# Schematic.net
KiCad netlist of a schematic drawn in Altium Designer
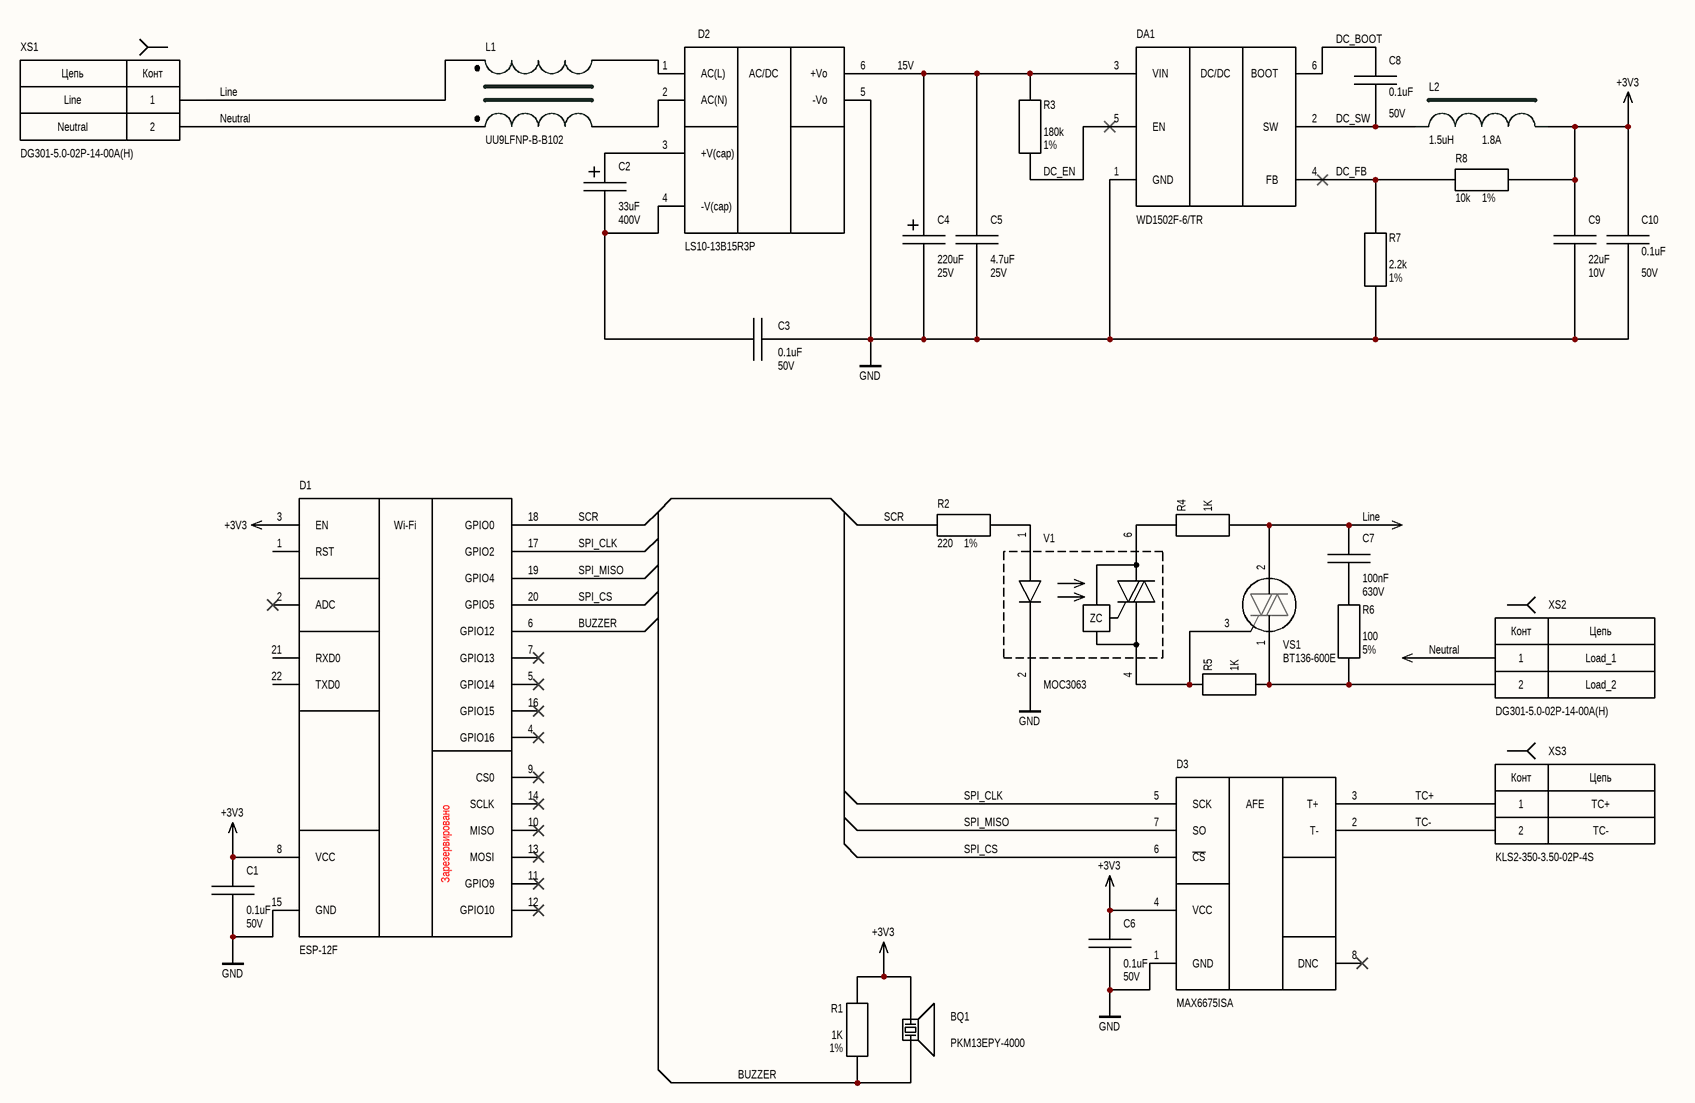
[diagram p0: Schematic.SchDoc]

(export (version "E")
  (design (tool "Eeschema 10.0.6"))
  (components
    (comp (ref "BQ1")
      (value "PKM13EPY-4000")
      (footprint "R_D12p6_H6p9_S5_d0p5")
      (fields (field (name "MANUFACTURER") "Murata"))
      (libsource (lib "CircuitCraft") (part "Buzzer"))
    )
    (comp (ref "C1")
      (value "0.1uF")
      (footprint "CAPC1608X09N")
      (fields
        (field (name "PART NUMBER") "0603-0.1uF-50V-10%-X7R")
        (field (name "VOLTAGE") "50V")
        (field (name "TOLERANCE") "10%")
        (field (name "PARAMETER") "50V")
      )
      (libsource (lib "CircuitCraft") (part "Capacitor"))
    )
    (comp (ref "C2")
      (value "33uF")
      (fields
        (field (name "PARAMETER") "400V")
        (field (name "PART NUMBER") "SHG33UF400V01EC1480")
        (field (name "MANUFACTURER") "KNSCHA")
        (field (name "VOLTAGE") "400V")
      )
      (libsource (lib "CircuitCraft") (part "Capacitor_pol"))
    )
    (comp (ref "C3")
      (value "0.1uF")
      (footprint "CAPC1608X09N")
      (fields
        (field (name "PART NUMBER") "0603-0.1uF-50V-10%-X7R")
        (field (name "VOLTAGE") "50V")
        (field (name "TOLERANCE") "10%")
        (field (name "PARAMETER") "50V")
      )
      (libsource (lib "CircuitCraft") (part "Capacitor"))
    )
    (comp (ref "C4")
      (value "220uF")
      (fields
        (field (name "PARAMETER") "25V")
        (field (name "PART NUMBER") "03EC0360")
        (field (name "MANUFACTURER") "KNSCHA")
        (field (name "VOLTAGE") "25V")
      )
      (libsource (lib "CircuitCraft") (part "Capacitor_pol"))
    )
    (comp (ref "C5")
      (value "4.7uF")
      (footprint "CAPC3216X19N")
      (fields
        (field (name "PARAMETER") "25V")
        (field (name "PART NUMBER") "1206-4.7uF-25V-10%-X7R")
        (field (name "VOLTAGE") "25V")
        (field (name "TOLERANCE") "10%")
      )
      (libsource (lib "CircuitCraft") (part "Capacitor"))
    )
    (comp (ref "C6")
      (value "0.1uF")
      (footprint "CAPC1608X09N")
      (fields
        (field (name "PART NUMBER") "0603-0.1uF-50V-10%-X7R")
        (field (name "VOLTAGE") "50V")
        (field (name "TOLERANCE") "10%")
        (field (name "PARAMETER") "50V")
      )
      (libsource (lib "CircuitCraft") (part "Capacitor"))
    )
    (comp (ref "C7")
      (value "100nF")
      (footprint "CAPRR1600W70L1750T600H1200")
      (fields
        (field (name "PARAMETER") "630V")
        (field (name "PART NUMBER") "MEF104J2J6AS6040A1")
        (field (name "MANUFACTURER") "JOEY")
        (field (name "VOLTAGE") "630V")
      )
      (libsource (lib "CircuitCraft") (part "Capacitor"))
    )
    (comp (ref "C8")
      (value "0.1uF")
      (footprint "CAPC1608X09N")
      (fields
        (field (name "PART NUMBER") "0603-0.1uF-50V-10%-X7R")
        (field (name "VOLTAGE") "50V")
        (field (name "TOLERANCE") "10%")
        (field (name "PARAMETER") "50V")
      )
      (libsource (lib "CircuitCraft") (part "Capacitor"))
    )
    (comp (ref "C9")
      (value "22uF")
      (footprint "CAPC3216X19N")
      (fields
        (field (name "PARAMETER") "10V")
        (field (name "PART NUMBER") "1206-22uF-10V-10%-X7R")
        (field (name "VOLTAGE") "10V")
        (field (name "TOLERANCE") "10%")
      )
      (libsource (lib "CircuitCraft") (part "Capacitor"))
    )
    (comp (ref "C10")
      (value "0.1uF")
      (footprint "CAPC1608X09N")
      (fields
        (field (name "PART NUMBER") "0603-0.1uF-50V-10%-X7R")
        (field (name "VOLTAGE") "50V")
        (field (name "TOLERANCE") "10%")
        (field (name "PARAMETER") "50V")
      )
      (libsource (lib "CircuitCraft") (part "Capacitor"))
    )
    (comp (ref "D1")
      (value "ESP-12F")
      (footprint "ESP-12F")
      (fields (field (name "MANUFACTURER") "Ai-Thinker"))
      (libsource (lib "CircuitCraft") (part "ESP-12F"))
    )
    (comp (ref "D2")
      (value "LS10-13B15R3P")
      (footprint "LS10-13BxxR3P_LUT")
      (fields (field (name "MANUFACTURER") "MORNSUN Guangzhou S& T"))
      (libsource (lib "CircuitCraft") (part "LS10-13BxxR3P"))
    )
    (comp (ref "D3")
      (value "MAX6675ISA")
      (footprint "SOIC8P127_490X600X175L83X42N")
      (fields (field (name "MANUFACTURER") "Analog Devices Inc./Maxim Integrated"))
      (libsource (lib "CircuitCraft") (part "MAX6675ISA"))
    )
    (comp (ref "DA1")
      (value "WD1502F-6/TR")
      (footprint "SOT23-6P95_280X90L45X42N")
      (fields (field (name "MANUFACTURER") "WILLSEMI(Will Semicon)"))
      (libsource (lib "CircuitCraft") (part "WD1502F-6_TR"))
    )
    (comp (ref "L1")
      (value "UU9LFNP-B-B102")
      (footprint "UU9LF")
      (fields (field (name "MANUFACTURER") "Sumida"))
      (libsource (lib "CircuitCraft") (part "Common Mode Choke"))
    )
    (comp (ref "L2")
      (value "1.5uH")
      (footprint "INDP400L400WX180_N")
      (fields
        (field (name "PARAMETER") "1.8A")
        (field (name "PART NUMBER") "SWPA4018S1R5NT")
        (field (name "MANUFACTURER") "Sunlord")
        (field (name "TOLERANCE") "30%")
      )
      (libsource (lib "CircuitCraft") (part "Inductor"))
    )
    (comp (ref "R1")
      (value "1K")
      (footprint "RESC1608X55N")
      (description "Resistor")
      (fields
        (field (name "PART NUMBER") "0603-1K-1%-1/10 W-100ppm")
        (field (name "TOLERANCE") "1%")
        (field (name "PARAMETER") "1%")
      )
      (libsource (lib "CircuitCraft") (part "Resistor"))
    )
    (comp (ref "R2")
      (value "220")
      (footprint "RESC1608X55N")
      (description "Resistor")
      (fields
        (field (name "PART NUMBER") "0603-220-1%-1/10 W-100ppm")
        (field (name "TOLERANCE") "1%")
        (field (name "PARAMETER") "1%")
      )
      (libsource (lib "CircuitCraft") (part "Resistor"))
    )
    (comp (ref "R3")
      (value "180k")
      (footprint "RESC1608X55N")
      (description "Resistor")
      (fields
        (field (name "PARAMETER") "1%")
        (field (name "PART NUMBER") "0603-180K-1%-1/10W-100ppm")
        (field (name "TOLERANCE") "1%")
      )
      (libsource (lib "CircuitCraft") (part "Resistor"))
    )
    (comp (ref "R4")
      (value "1K")
      (footprint "RESC1608X55N")
      (description "Resistor")
      (fields (field (name "PART NUMBER") "0603-1K-1%-1/10 W-100ppm") (field (name "TOLERANCE") "1%"))
      (libsource (lib "CircuitCraft") (part "Resistor"))
    )
    (comp (ref "R5")
      (value "1K")
      (footprint "RESC1608X55N")
      (description "Resistor")
      (fields (field (name "PART NUMBER") "0603-1K-1%-1/10 W-100ppm") (field (name "TOLERANCE") "1%"))
      (libsource (lib "CircuitCraft") (part "Resistor"))
    )
    (comp (ref "R6")
      (value "100")
      (footprint "MF-05W_RESAD1400W60L1000D500")
      (description "Resistor")
      (fields
        (field (name "PARAMETER") "5%")
        (field (name "PART NUMBER") "MF0W2JJ0101A10")
        (field (name "MANUFACTURER") "UNI-ROYAL(Uniroyal Elec)")
      )
      (libsource (lib "CircuitCraft") (part "Resistor"))
    )
    (comp (ref "R7")
      (value "2.2k")
      (footprint "RESC1608X55N")
      (description "Resistor")
      (fields
        (field (name "PARAMETER") "1%")
        (field (name "PART NUMBER") "0603-2.2K-1%-1/10W-100ppm")
        (field (name "TOLERANCE") "1%")
      )
      (libsource (lib "CircuitCraft") (part "Resistor"))
    )
    (comp (ref "R8")
      (value "10k")
      (footprint "RESC1608X55N")
      (description "Resistor")
      (fields
        (field (name "PARAMETER") "1%")
        (field (name "PART NUMBER") "0603-10k-1%-1/10 W-100ppm")
        (field (name "TOLERANCE") "1%")
      )
      (libsource (lib "CircuitCraft") (part "Resistor"))
    )
    (comp (ref "V1")
      (value "MOC3063")
      (footprint "DIP-6_DIP762W50P254L735H400Q6")
      (description "Оптрон тиристорный")
      (fields (field (name "MANUFACTURER") "Lite-On"))
      (libsource (lib "CircuitCraft") (part "MOC3063"))
    )
    (comp (ref "VS1")
      (value "BT136-600Е")
      (footprint "TO-220C_TO254_440P1040X460X2000-3")
      (fields (field (name "MANUFACTURER") "WEIDA"))
      (libsource (lib "CircuitCraft") (part "Triac_1T12T23G"))
    )
    (comp (ref "XS1")
      (value "DG301-5.0-02P-14-00A(H)")
      (footprint "DG301-5.0-02P")
      (fields (field (name "MANUFACTURER") "DEGSON"))
      (libsource (lib "CircuitCraft") (part "CONN_2PIN_F"))
    )
    (comp (ref "XS2")
      (value "DG301-5.0-02P-14-00A(H)")
      (footprint "DG301-5.0-02P")
      (fields (field (name "MANUFACTURER") "DEGSON"))
      (libsource (lib "CircuitCraft") (part "CONN_2PIN_F"))
    )
    (comp (ref "XS3")
      (value "KLS2-350-3.50-02P-4S")
      (footprint "KLS2-350-3.50-02P-4S")
      (fields (field (name "MANUFACTURER") "KLS"))
      (libsource (lib "CircuitCraft") (part "CONN_2PIN_F"))
    )
  )
  (nets
    (net (code "1") (name "+3V3") (class "Default")
      (node (ref "BQ1") (pin "1") (pinfunction "1_1") (pintype "passive"))
      (node (ref "C1") (pin "1") (pinfunction "1_1") (pintype "passive"))
      (node (ref "C10") (pin "1") (pinfunction "1_1") (pintype "passive"))
      (node (ref "C6") (pin "1") (pinfunction "1_1") (pintype "passive"))
      (node (ref "C9") (pin "1") (pinfunction "1_1") (pintype "passive"))
      (node (ref "D1") (pin "3") (pinfunction "EN_3") (pintype "passive"))
      (node (ref "D1") (pin "8") (pinfunction "VCC_8") (pintype "passive"))
      (node (ref "D3") (pin "4") (pinfunction "VCC_4") (pintype "passive"))
      (node (ref "L2") (pin "2") (pinfunction "2_2") (pintype "passive"))
      (node (ref "R1") (pin "2") (pinfunction "2_2") (pintype "passive"))
      (node (ref "R8") (pin "2") (pinfunction "2_2") (pintype "passive"))
    )
    (net (code "2") (name "/15V") (class "Default")
      (node (ref "C4") (pin "2") (pinfunction "2_2") (pintype "passive"))
      (node (ref "C5") (pin "1") (pinfunction "1_1") (pintype "passive"))
      (node (ref "D2") (pin "6") (pinfunction "+Vo_6") (pintype "passive"))
      (node (ref "DA1") (pin "3") (pinfunction "VIN_3") (pintype "passive"))
      (node (ref "R3") (pin "2") (pinfunction "2_2") (pintype "passive"))
    )
    (net (code "3") (name "/BUZZER") (class "Default")
      (node (ref "BQ1") (pin "2") (pinfunction "2_2") (pintype "passive"))
      (node (ref "D1") (pin "6") (pinfunction "GPIO12_6") (pintype "passive"))
      (node (ref "R1") (pin "1") (pinfunction "1_1") (pintype "passive"))
    )
    (net (code "4") (name "/DC_BOOT") (class "Default")
      (node (ref "C8") (pin "1") (pinfunction "1_1") (pintype "passive"))
      (node (ref "DA1") (pin "6") (pinfunction "BOOT_6") (pintype "passive"))
    )
    (net (code "5") (name "/DC_EN") (class "Default")
      (node (ref "DA1") (pin "5") (pinfunction "EN_5") (pintype "passive"))
      (node (ref "R3") (pin "1") (pinfunction "1_1") (pintype "passive"))
    )
    (net (code "6") (name "/DC_FB") (class "Default")
      (node (ref "DA1") (pin "4") (pinfunction "FB_4") (pintype "passive"))
      (node (ref "R7") (pin "2") (pinfunction "2_2") (pintype "passive"))
      (node (ref "R8") (pin "1") (pinfunction "1_1") (pintype "passive"))
    )
    (net (code "7") (name "/DC_SW") (class "Default")
      (node (ref "C8") (pin "2") (pinfunction "2_2") (pintype "passive"))
      (node (ref "DA1") (pin "2") (pinfunction "SW_2") (pintype "passive"))
      (node (ref "L2") (pin "1") (pinfunction "1_1") (pintype "passive"))
    )
    (net (code "8") (name "/Line") (class "Default")
      (node (ref "C7") (pin "1") (pinfunction "1_1") (pintype "passive"))
      (node (ref "L1") (pin "1") (pinfunction "1_1") (pintype "passive"))
      (node (ref "R4") (pin "1") (pinfunction "1_1") (pintype "passive"))
      (node (ref "VS1") (pin "2") (pinfunction "T2_2") (pintype "passive"))
      (node (ref "XS1") (pin "1") (pinfunction "1_1") (pintype "passive"))
    )
    (net (code "9") (name "/Neutral") (class "Default")
      (node (ref "L1") (pin "4") (pinfunction "4_4") (pintype "passive"))
      (node (ref "XS1") (pin "2") (pinfunction "2_2") (pintype "passive"))
      (node (ref "XS2") (pin "1") (pinfunction "1_1") (pintype "passive"))
    )
    (net (code "10") (name "/SCR") (class "Default")
      (node (ref "D1") (pin "18") (pinfunction "GPIO0_18") (pintype "passive"))
      (node (ref "R2") (pin "1") (pinfunction "1_1") (pintype "passive"))
    )
    (net (code "11") (name "/SPI_CLK") (class "Default")
      (node (ref "D1") (pin "17") (pinfunction "GPIO2_17") (pintype "passive"))
      (node (ref "D3") (pin "5") (pinfunction "SCK_5") (pintype "passive"))
    )
    (net (code "12") (name "/SPI_CS") (class "Default")
      (node (ref "D1") (pin "20") (pinfunction "GPIO5_20") (pintype "passive"))
      (node (ref "D3") (pin "6") (pinfunction "~{CS}_6") (pintype "passive"))
    )
    (net (code "13") (name "/SPI_MISO") (class "Default")
      (node (ref "D1") (pin "19") (pinfunction "GPIO4_19") (pintype "passive"))
      (node (ref "D3") (pin "7") (pinfunction "SO_7") (pintype "passive"))
    )
    (net (code "14") (name "/TC+") (class "Default")
      (node (ref "D3") (pin "3") (pinfunction "T+_3") (pintype "passive"))
      (node (ref "XS3") (pin "1") (pinfunction "1_1") (pintype "passive"))
    )
    (net (code "15") (name "/TC-") (class "Default")
      (node (ref "D3") (pin "2") (pinfunction "T-_2") (pintype "passive"))
      (node (ref "XS3") (pin "2") (pinfunction "2_2") (pintype "passive"))
    )
    (net (code "16") (name "GND") (class "Default")
      (node (ref "C1") (pin "2") (pinfunction "2_2") (pintype "passive"))
      (node (ref "C10") (pin "2") (pinfunction "2_2") (pintype "passive"))
      (node (ref "C3") (pin "2") (pinfunction "2_2") (pintype "passive"))
      (node (ref "C4") (pin "1") (pinfunction "1_1") (pintype "passive"))
      (node (ref "C5") (pin "2") (pinfunction "2_2") (pintype "passive"))
      (node (ref "C6") (pin "2") (pinfunction "2_2") (pintype "passive"))
      (node (ref "C9") (pin "2") (pinfunction "2_2") (pintype "passive"))
      (node (ref "D1") (pin "15") (pinfunction "GND_15") (pintype "passive"))
      (node (ref "D2") (pin "5") (pinfunction "-Vo_5") (pintype "passive"))
      (node (ref "D3") (pin "1") (pinfunction "GND_1") (pintype "passive"))
      (node (ref "DA1") (pin "1") (pinfunction "GND_1") (pintype "passive"))
      (node (ref "R7") (pin "1") (pinfunction "1_1") (pintype "passive"))
      (node (ref "V1") (pin "2") (pinfunction "-_2") (pintype "passive"))
    )
    (net (code "17") (name "Net-(C7-Pad2)") (class "Default")
      (node (ref "C7") (pin "2") (pinfunction "2_2") (pintype "passive"))
      (node (ref "R6") (pin "2") (pinfunction "2_2") (pintype "passive"))
    )
    (net (code "18") (name "Net-(D2-+V(cap))") (class "Default")
      (node (ref "C2") (pin "2") (pinfunction "2_2") (pintype "passive"))
      (node (ref "D2") (pin "3") (pinfunction "+V(cap)_3") (pintype "passive"))
    )
    (net (code "19") (name "Net-(D2--V(cap))") (class "Default")
      (node (ref "C2") (pin "1") (pinfunction "1_1") (pintype "passive"))
      (node (ref "C3") (pin "1") (pinfunction "1_1") (pintype "passive"))
      (node (ref "D2") (pin "4") (pinfunction "-V(cap)_4") (pintype "passive"))
    )
    (net (code "20") (name "Net-(D2-AC(L))") (class "Default")
      (node (ref "D2") (pin "1") (pinfunction "AC(L)_1") (pintype "passive"))
      (node (ref "L1") (pin "2") (pinfunction "2_2") (pintype "passive"))
    )
    (net (code "21") (name "Net-(D2-AC(N))") (class "Default")
      (node (ref "D2") (pin "2") (pinfunction "AC(N)_2") (pintype "passive"))
      (node (ref "L1") (pin "3") (pinfunction "3_3") (pintype "passive"))
    )
    (net (code "22") (name "Net-(R4-Pad2)") (class "Default")
      (node (ref "R4") (pin "2") (pinfunction "2_2") (pintype "passive"))
      (node (ref "V1") (pin "6") (pintype "passive"))
    )
    (net (code "23") (name "Net-(V1-+)") (class "Default")
      (node (ref "R2") (pin "2") (pinfunction "2_2") (pintype "passive"))
      (node (ref "V1") (pin "1") (pinfunction "+_1") (pintype "passive"))
    )
    (net (code "24") (name "Net-(VS1-G)") (class "Default")
      (node (ref "R5") (pin "2") (pinfunction "2_2") (pintype "passive"))
      (node (ref "V1") (pin "4") (pintype "passive"))
      (node (ref "VS1") (pin "3") (pinfunction "G_3") (pintype "passive"))
    )
    (net (code "25") (name "Net-(VS1-T1)") (class "Default")
      (node (ref "R5") (pin "1") (pinfunction "1_1") (pintype "passive"))
      (node (ref "R6") (pin "1") (pinfunction "1_1") (pintype "passive"))
      (node (ref "VS1") (pin "1") (pinfunction "T1_1") (pintype "passive"))
      (node (ref "XS2") (pin "2") (pinfunction "2_2") (pintype "passive"))
    )
    (net (code "26") (name "unconnected-(D1-ADC-Pad2)") (class "Default")
      (node (ref "D1") (pin "2") (pinfunction "ADC_2") (pintype "passive+no_connect"))
    )
    (net (code "27") (name "unconnected-(D1-CS0-Pad9)") (class "Default")
      (node (ref "D1") (pin "9") (pinfunction "CS0_9") (pintype "passive+no_connect"))
    )
    (net (code "28") (name "unconnected-(D1-GPIO9-Pad11)") (class "Default")
      (node (ref "D1") (pin "11") (pinfunction "GPIO9_11") (pintype "passive+no_connect"))
    )
    (net (code "29") (name "unconnected-(D1-GPIO10-Pad12)") (class "Default")
      (node (ref "D1") (pin "12") (pinfunction "GPIO10_12") (pintype "passive+no_connect"))
    )
    (net (code "30") (name "unconnected-(D1-GPIO13-Pad7)") (class "Default")
      (node (ref "D1") (pin "7") (pinfunction "GPIO13_7") (pintype "passive+no_connect"))
    )
    (net (code "31") (name "unconnected-(D1-GPIO14-Pad5)") (class "Default")
      (node (ref "D1") (pin "5") (pinfunction "GPIO14_5") (pintype "passive+no_connect"))
    )
    (net (code "32") (name "unconnected-(D1-GPIO15-Pad16)") (class "Default")
      (node (ref "D1") (pin "16") (pinfunction "GPIO15_16") (pintype "passive+no_connect"))
    )
    (net (code "33") (name "unconnected-(D1-GPIO16-Pad4)") (class "Default")
      (node (ref "D1") (pin "4") (pinfunction "GPIO16_4") (pintype "passive+no_connect"))
    )
    (net (code "34") (name "unconnected-(D1-MISO-Pad10)") (class "Default")
      (node (ref "D1") (pin "10") (pinfunction "MISO_10") (pintype "passive+no_connect"))
    )
    (net (code "35") (name "unconnected-(D1-MOSI-Pad13)") (class "Default")
      (node (ref "D1") (pin "13") (pinfunction "MOSI_13") (pintype "passive+no_connect"))
    )
    (net (code "36") (name "unconnected-(D1-RST-Pad1)") (class "Default")
      (node (ref "D1") (pin "1") (pinfunction "RST_1") (pintype "passive"))
    )
    (net (code "37") (name "unconnected-(D1-RXD0-Pad21)") (class "Default")
      (node (ref "D1") (pin "21") (pinfunction "RXD0_21") (pintype "passive"))
    )
    (net (code "38") (name "unconnected-(D1-SCLK-Pad14)") (class "Default")
      (node (ref "D1") (pin "14") (pinfunction "SCLK_14") (pintype "passive+no_connect"))
    )
    (net (code "39") (name "unconnected-(D1-TXD0-Pad22)") (class "Default")
      (node (ref "D1") (pin "22") (pinfunction "TXD0_22") (pintype "passive"))
    )
    (net (code "40") (name "unconnected-(D3-DNC-Pad8)") (class "Default")
      (node (ref "D3") (pin "8") (pinfunction "DNC_8") (pintype "passive+no_connect"))
    )
  )
)
